# audio_amplifier.net
KiCad netlist of a schematic drawn in Altium Designer
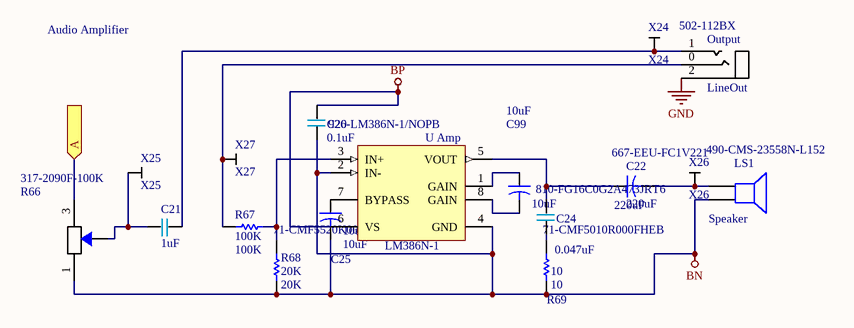
[diagram p0: audio_amplifier.SchDoc]

(export (version "E")
  (design (tool "Eeschema 10.0.6"))
  (components
    (comp (ref "C20")
      (value "0.1uF")
      (footprint "Cap Film 5")
      (fields (field (name "Comment") ".1uF"))
      (libsource (lib "MyLibrary") (part "Cap Film 5"))
    )
    (comp (ref "C21")
      (value "1uF")
      (footprint "Cap Film 5")
      (fields
        (field (name "MANUFACTURER") "Panasonic")
        (field (name "MANUFACTURER PART NUMBER") "ECQ-E2105KF")
      )
      (libsource (lib "MyLibrary") (part "Cap Film 5"))
    )
    (comp (ref "C22")
      (value "220uF")
      (footprint "CAPR5-4X5")
      (description "Capacitor")
      (fields
        (field (name "ALTIUM_VALUE") "220uF")
        (field (name "SUPPLIER PART NUMBER 1") "667-EEU-FC1V221")
        (field (name "MANUFACTURER") "Panasonic")
        (field (name "MANUFACTURER PART NUMBER") "EEU-FC1V221")
        (field (name "PUBLISHER") "Altium Limited")
      )
      (libsource (lib "Miscellaneous Devices") (part "Cap2"))
    )
    (comp (ref "C24")
      (value "0.047uF")
      (footprint "Cap Film 5")
      (fields
        (field (name "SUPPLIER PART NUMBER 1") "810-FG16C0G2A473JRT6")
        (field (name "MANUFACTURER") "TDK")
        (field (name "MANUFACTURER PART NUMBER") "FG16C0G2A473JRT06")
        (field (name "TOLERANCE") "5 %")
      )
      (libsource (lib "MyLibrary") (part "Cap Film 5"))
    )
    (comp (ref "C25")
      (value "10uF")
      (footprint "CAPR5-4X5")
      (description "Capacitor")
      (fields
        (field (name "ALTIUM_VALUE") "10uF")
        (field (name "MANUFACTURER") "Panasonic")
        (field (name "MANUFACTURER PART NUMBER") "ECA-1VM100")
        (field (name "PUBLISHER") "Altium Limited")
      )
      (libsource (lib "Miscellaneous Devices") (part "Cap2"))
    )
    (comp (ref "C99")
      (value "10uF")
      (footprint "CAPR5-4X5")
      (description "Capacitor")
      (fields
        (field (name "ALTIUM_VALUE") "10uF")
        (field (name "MANUFACTURER") "Panasonic")
        (field (name "MANUFACTURER PART NUMBER") "ECA-1VM100")
        (field (name "PUBLISHER") "Altium Limited")
      )
      (libsource (lib "Miscellaneous Devices") (part "Cap2"))
    )
    (comp (ref "LS1")
      (value "Speaker")
      (footprint "PIN2")
      (description "Loudspeaker")
      (fields
        (field (name "SUPPLIER PART NUMBER 1") "490-CMS-23558N-L152")
        (field (name "MANUFACTURER") "CUI")
        (field (name "MANUFACTURER PART NUMBER") "CMS-23558N-L152")
        (field (name "PUBLISHER") "Altium Limited")
      )
      (libsource (lib "Miscellaneous Devices") (part "Speaker"))
    )
    (comp (ref "Output")
      (value "LineOut")
      (footprint "Stereo Jack")
      (description "Stereo Jack")
      (fields
        (field (name "SUPPLIER PART NUMBER 1") "502-112BX")
        (field (name "MANUFACTURER") "Switchcraft")
        (field (name "MANUFACTURER PART NUMBER") "112BX")
      )
      (libsource (lib "MyLibrary") (part "Stereo Jack"))
    )
    (comp (ref "R66")
      (value "100K")
      (footprint "Potentiometer")
      (description "My Own")
      (fields
        (field (name "SUPPLIER PART NUMBER 1") "317-2090F-100K")
        (field (name "MANUFACTURER") "Alpha (Taiwan)")
        (field (name "MANUFACTURER PART NUMBER") "RV09AF-40-20K-B100K")
      )
      (libsource (lib "MyLibrary") (part "Potentiometer"))
    )
    (comp (ref "R67")
      (value "100K")
      (footprint "AXIAL-0.3")
      (description "Resistor")
      (fields
        (field (name "ALTIUM_VALUE") "100K")
        (field (name "MANUFACTURER") "Vishay / Dale")
        (field (name "MANUFACTURER PART NUMBER") "CMF55100K00FHEK")
        (field (name "PUBLISHER") "Altium Limited")
      )
      (libsource (lib "Miscellaneous Devices") (part "Res1"))
    )
    (comp (ref "R68")
      (value "20K")
      (footprint "AXIAL-0.3")
      (description "Resistor")
      (fields
        (field (name "ALTIUM_VALUE") "20K")
        (field (name "SUPPLIER PART NUMBER 1") "71-CMF5520K000FHEB")
        (field (name "MANUFACTURER") "Vishay / Dale")
        (field (name "MANUFACTURER PART NUMBER") "CMF5520K000FHEB")
        (field (name "PUBLISHER") "Altium Limited")
      )
      (libsource (lib "Miscellaneous Devices") (part "Res1"))
    )
    (comp (ref "R69")
      (value "10")
      (footprint "AXIAL-0.3")
      (description "Metal Film Resistors - Through Hole 1/4watt 10Kohms 5% Rated to 1/2watt")
      (fields
        (field (name "ALTIUM_VALUE") "10")
        (field (name "SUPPLIER PART NUMBER 1") "71-CMF5010R000FHEB")
        (field (name "MANUFACTURER") "Vishay / Dale")
        (field (name "MANUFACTURER PART NUMBER") "CMF5010R000FHEB")
        (field (name "PUBLISHER") "Altium Limited")
      )
      (libsource (lib "Miscellaneous Devices") (part "Res1"))
    )
    (comp (ref "U Amp")
      (value "LM386N-1")
      (footprint "N08E")
      (description "Low Voltage Audio Power Amplifier, 8-pin MDIP")
      (fields
        (field (name "MANUFACTURER") "National Semiconductor")
        (field (name "SUPPLIER PART NUMBER 1") "926-LM386N-1/NOPB")
        (field (name "MANUFACTURER PART NUMBER") "LM386N-1/NOPB")
      )
      (libsource (lib "National Semiconductor Audio") (part "LM386N-1"))
    )
    (comp (ref "X24") (value "X24") (footprint "Pad") (libsource (lib "MyLibrary") (part "Pad")))
    (comp (ref "X25") (value "X25") (footprint "Pad") (libsource (lib "MyLibrary") (part "Pad")))
    (comp (ref "X26") (value "X26") (footprint "Pad") (libsource (lib "MyLibrary") (part "Pad")))
    (comp (ref "X27") (value "X27") (footprint "Pad") (libsource (lib "MyLibrary") (part "Pad")))
  )
  (nets
    (net (code "1") (name "/A") (class "Default")
      (node (ref "R66") (pin "3") (pinfunction "3_3") (pintype "passive"))
    )
    (net (code "2") (name "BN") (class "Default")
      (node (ref "C20") (pin "1") (pinfunction "1_1") (pintype "passive"))
      (node (ref "C25") (pin "2") (pinfunction "2_2") (pintype "passive"))
      (node (ref "LS1") (pin "2") (pinfunction "2_2") (pintype "passive"))
      (node (ref "R66") (pin "1") (pinfunction "1_1") (pintype "passive"))
      (node (ref "R68") (pin "1") (pinfunction "1_1") (pintype "passive"))
      (node (ref "R69") (pin "1") (pinfunction "1_1") (pintype "passive"))
      (node (ref "U Amp") (pin "2") (pinfunction "IN-_2") (pintype "input"))
      (node (ref "U Amp") (pin "4") (pinfunction "GND_4") (pintype "power_in"))
    )
    (net (code "3") (name "BP") (class "Default")
      (node (ref "C20") (pin "2") (pinfunction "2_2") (pintype "passive"))
      (node (ref "U Amp") (pin "6") (pinfunction "VS_6") (pintype "power_in"))
    )
    (net (code "4") (name "GND") (class "Default")
      (node (ref "Output") (pin "2") (pinfunction "Sleeve_2") (pintype "passive"))
    )
    (net (code "5") (name "Net-(C21-Pad2)") (class "Default")
      (node (ref "C21") (pin "2") (pinfunction "2_2") (pintype "passive"))
      (node (ref "R66") (pin "2") (pinfunction "2_2") (pintype "passive"))
      (node (ref "X25") (pin "1") (pinfunction "1_1") (pintype "passive"))
    )
    (net (code "6") (name "Net-(C22-Pad2)") (class "Default")
      (node (ref "C22") (pin "2") (pinfunction "2_2") (pintype "passive"))
      (node (ref "LS1") (pin "1") (pinfunction "1_1") (pintype "passive"))
      (node (ref "X26") (pin "1") (pinfunction "1_1") (pintype "passive"))
    )
    (net (code "7") (name "Net-(C24-Pad1)") (class "Default")
      (node (ref "C24") (pin "1") (pinfunction "1_1") (pintype "passive"))
      (node (ref "R69") (pin "2") (pinfunction "2_2") (pintype "passive"))
    )
    (net (code "8") (name "Net-(C99-Pad1)") (class "Default")
      (node (ref "C99") (pin "1") (pinfunction "1_1") (pintype "passive"))
      (node (ref "U Amp") (pin "1") (pinfunction "GAIN_1") (pintype "passive"))
    )
    (net (code "9") (name "Net-(C99-Pad2)") (class "Default")
      (node (ref "C99") (pin "2") (pinfunction "2_2") (pintype "passive"))
      (node (ref "U Amp") (pin "8") (pinfunction "GAIN_8") (pintype "passive"))
    )
    (net (code "10") (name "Net-(Output-Ring)") (class "Default")
      (node (ref "Output") (pin "0") (pinfunction "Ring_0") (pintype "passive"))
      (node (ref "R67") (pin "1") (pinfunction "1_1") (pintype "passive"))
      (node (ref "X27") (pin "1") (pinfunction "1_1") (pintype "passive"))
    )
    (net (code "11") (name "Net-(Output-Tip)") (class "Default")
      (node (ref "C21") (pin "1") (pinfunction "1_1") (pintype "passive"))
      (node (ref "Output") (pin "1") (pinfunction "Tip_1") (pintype "passive"))
      (node (ref "X24") (pin "1") (pinfunction "1_1") (pintype "passive"))
    )
    (net (code "12") (name "Net-(U Amp-BYPASS)") (class "Default")
      (node (ref "C25") (pin "1") (pinfunction "1_1") (pintype "passive"))
      (node (ref "U Amp") (pin "7") (pinfunction "BYPASS_7") (pintype "passive"))
    )
    (net (code "13") (name "Net-(U Amp-IN+)") (class "Default")
      (node (ref "R67") (pin "2") (pinfunction "2_2") (pintype "passive"))
      (node (ref "R68") (pin "2") (pinfunction "2_2") (pintype "passive"))
      (node (ref "U Amp") (pin "3") (pinfunction "IN+_3") (pintype "input"))
    )
    (net (code "14") (name "Net-(U Amp-VOUT)") (class "Default")
      (node (ref "C22") (pin "1") (pinfunction "1_1") (pintype "passive"))
      (node (ref "C24") (pin "2") (pinfunction "2_2") (pintype "passive"))
      (node (ref "U Amp") (pin "5") (pinfunction "VOUT_5") (pintype "output"))
    )
  )
)
